# luxo.net
KiCad netlist of a schematic drawn in EAGLE
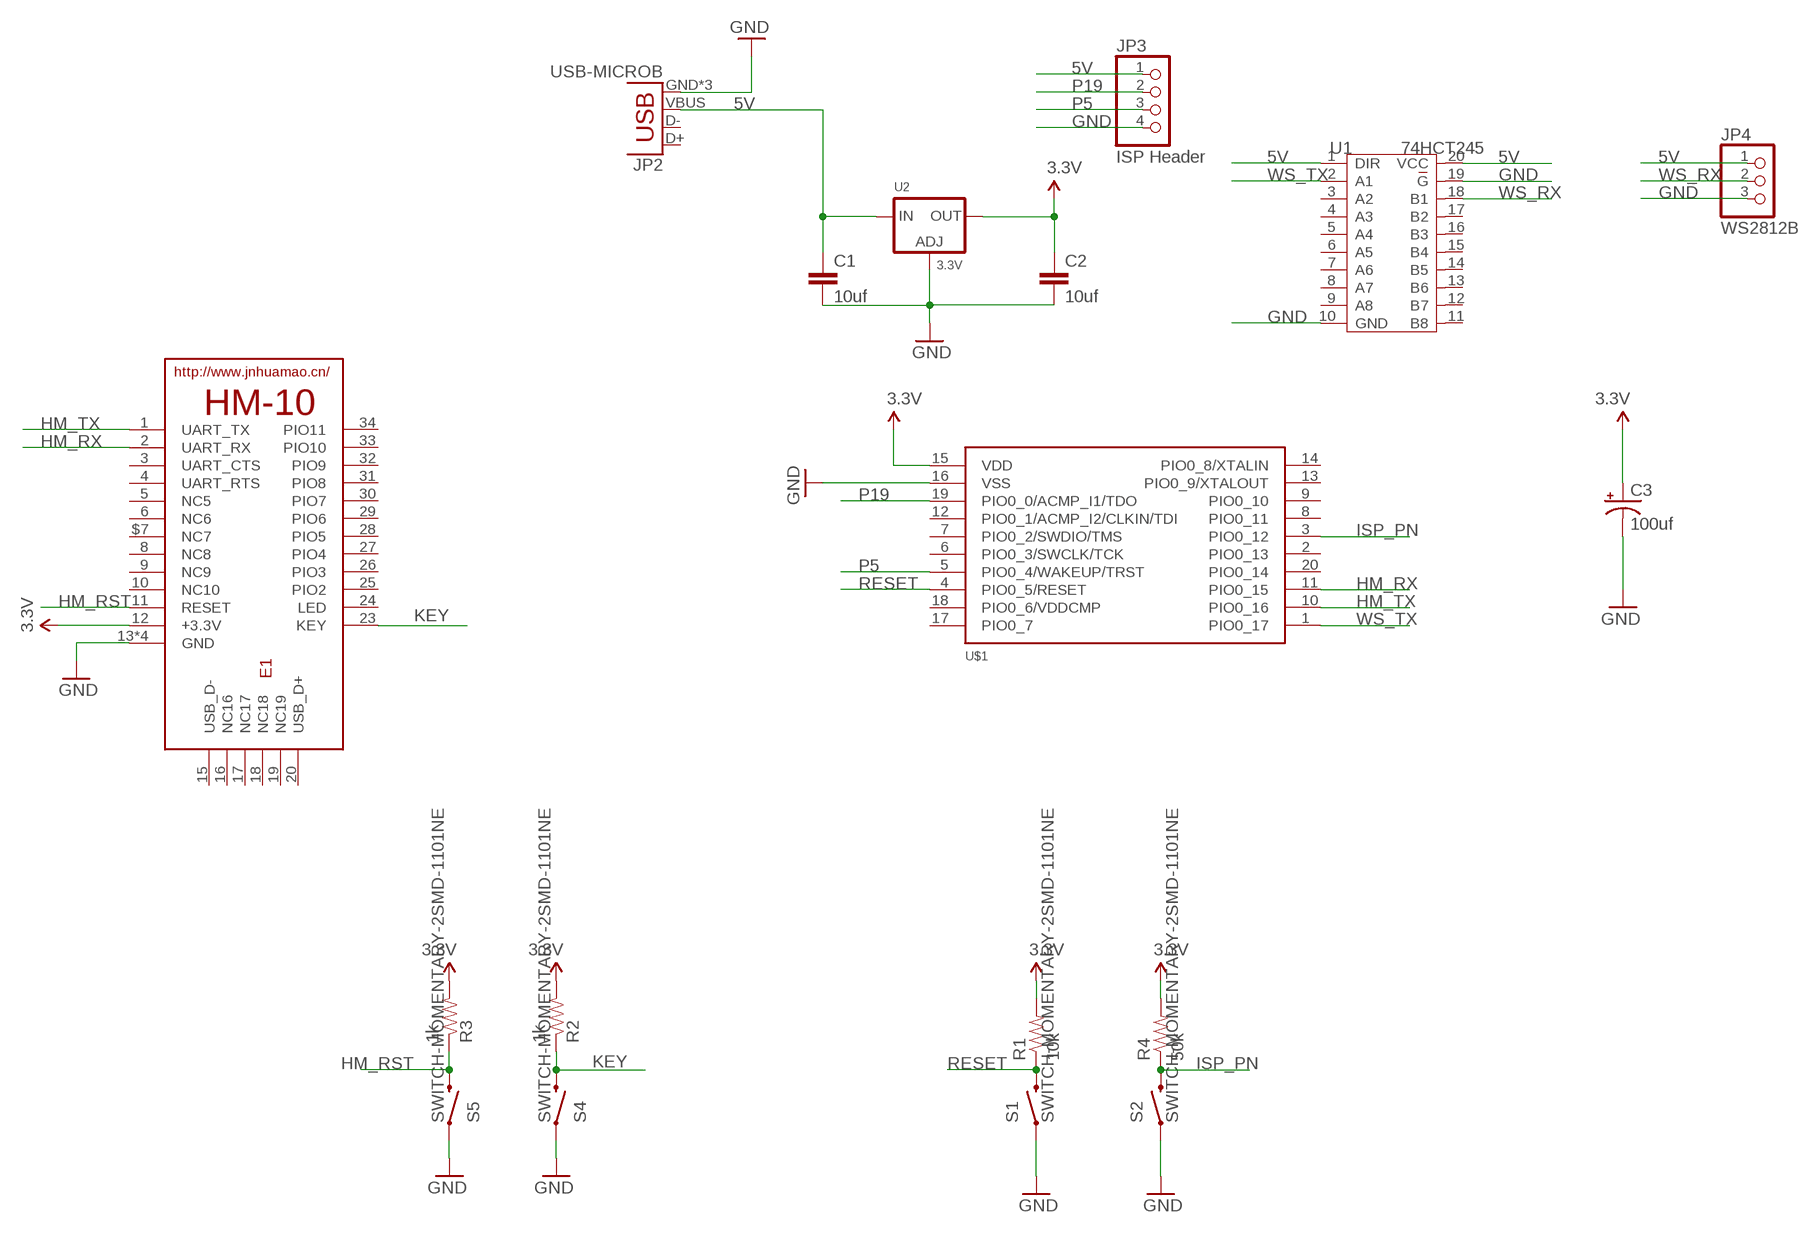
[diagram p0: schematic, sheet 1]

(export (version "E")
  (design (tool "Eeschema 10.0.6"))
  (components
    (comp (ref "C1")
      (value "10uf")
      (footprint "eagle-import:0805-CAP")
      (libsource (lib "eagle-import") (part "10UF10V10%(0805)"))
    )
    (comp (ref "C2")
      (value "10uf")
      (footprint "eagle-import:0805-CAP")
      (libsource (lib "eagle-import") (part "10UF10V10%(0805)"))
    )
    (comp (ref "C3")
      (value "100uf")
      (footprint "eagle-import:CPOL-RADIAL-100UF-25V")
      (libsource (lib "eagle-import") (part "100UF-25V-20%(PTH)"))
    )
    (comp (ref "E1")
      (value "HM-10-BOARD")
      (footprint "eagle-import:26.9X13X2.2_BOARD")
      (libsource (lib "eagle-import") (part "HM-10-BOARD"))
    )
    (comp (ref "JP2")
      (value "USB-MICROB")
      (footprint "eagle-import:USB-MICROB")
      (libsource (lib "eagle-import") (part "USB-MICROB"))
    )
    (comp (ref "JP3")
      (value "ISP Header")
      (footprint "eagle-import:1X04_ROUND")
      (libsource (lib "eagle-import") (part "HEADER-1X4ROUND"))
    )
    (comp (ref "JP4")
      (value "WS2812B")
      (footprint "eagle-import:1X03_OVAL")
      (libsource (lib "eagle-import") (part "HEADER-1X3"))
    )
    (comp (ref "R1")
      (value "10k")
      (footprint "eagle-import:0805")
      (libsource (lib "eagle-import") (part "RESISTOR0805-RES"))
    )
    (comp (ref "R2")
      (value "1k")
      (footprint "eagle-import:0805")
      (libsource (lib "eagle-import") (part "RESISTOR0805-RES"))
    )
    (comp (ref "R3")
      (value "1k")
      (footprint "eagle-import:0805")
      (libsource (lib "eagle-import") (part "RESISTOR0805-RES"))
    )
    (comp (ref "R4")
      (value "50k")
      (footprint "eagle-import:0805")
      (libsource (lib "eagle-import") (part "RESISTOR0805-RES"))
    )
    (comp (ref "S1")
      (value "SWITCH-MOMENTARY-2SMD-1101NE")
      (footprint "eagle-import:TACTILE-SWITCH-1101NE")
      (libsource (lib "eagle-import") (part "SWITCH-MOMENTARY-2SMD-1101NE"))
    )
    (comp (ref "S2")
      (value "SWITCH-MOMENTARY-2SMD-1101NE")
      (footprint "eagle-import:TACTILE-SWITCH-1101NE")
      (libsource (lib "eagle-import") (part "SWITCH-MOMENTARY-2SMD-1101NE"))
    )
    (comp (ref "S4")
      (value "SWITCH-MOMENTARY-2SMD-1101NE")
      (footprint "eagle-import:TACTILE-SWITCH-1101NE")
      (libsource (lib "eagle-import") (part "SWITCH-MOMENTARY-2SMD-1101NE"))
    )
    (comp (ref "S5")
      (value "SWITCH-MOMENTARY-2SMD-1101NE")
      (footprint "eagle-import:TACTILE-SWITCH-1101NE")
      (libsource (lib "eagle-import") (part "SWITCH-MOMENTARY-2SMD-1101NE"))
    )
    (comp (ref "U$1")
      (value "LPC812M101JDH20")
      (footprint "eagle-import:TSSOP20")
      (libsource (lib "eagle-import") (part "LPC812M101JDH20"))
    )
    (comp (ref "U1")
      (value "74HCT245")
      (footprint "eagle-import:SOP20-10.65")
      (libsource (lib "eagle-import") (part "74ACT245-SOP20"))
    )
    (comp (ref "U2")
      (value "3.3V")
      (footprint "eagle-import:SOT223-W")
      (libsource (lib "eagle-import") (part "LM1117SOT223-WAVE"))
    )
  )
  (nets
    (net (code "1") (name "/5V") (class "Default")
      (node (ref "C1") (pin "1") (pinfunction "1_1") (pintype "passive"))
      (node (ref "JP2") (pin "VBUS") (pinfunction "VBUS_VBUS") (pintype "bidirectional"))
      (node (ref "JP3") (pin "1") (pinfunction "1_1") (pintype "passive"))
      (node (ref "JP4") (pin "1") (pinfunction "1_1") (pintype "passive"))
      (node (ref "U1") (pin "1") (pinfunction "DIR_1") (pintype "input"))
      (node (ref "U1") (pin "20") (pinfunction "VCC_20") (pintype "power_in"))
      (node (ref "U2") (pin "3") (pinfunction "IN_3") (pintype "input"))
    )
    (net (code "2") (name "/HM_RST") (class "Default")
      (node (ref "E1") (pin "11") (pinfunction "RESET_11") (pintype "bidirectional"))
      (node (ref "R3") (pin "1") (pinfunction "1_1") (pintype "passive"))
      (node (ref "S5") (pin "2") (pinfunction "2_2") (pintype "passive"))
    )
    (net (code "3") (name "/HM_RX") (class "Default")
      (node (ref "E1") (pin "2") (pinfunction "UART_RX_2") (pintype "bidirectional"))
      (node (ref "U$1") (pin "11") (pinfunction "PIO0_15_11") (pintype "bidirectional"))
    )
    (net (code "4") (name "/HM_TX") (class "Default")
      (node (ref "E1") (pin "1") (pinfunction "UART_TX_1") (pintype "bidirectional"))
      (node (ref "U$1") (pin "10") (pinfunction "PIO0_16_10") (pintype "bidirectional"))
    )
    (net (code "5") (name "/ISP_PN") (class "Default")
      (node (ref "R4") (pin "1") (pinfunction "1_1") (pintype "passive"))
      (node (ref "S2") (pin "2") (pinfunction "2_2") (pintype "passive"))
      (node (ref "U$1") (pin "3") (pinfunction "PIO0_12_3") (pintype "bidirectional"))
    )
    (net (code "6") (name "/KEY") (class "Default")
      (node (ref "E1") (pin "23") (pinfunction "KEY_23") (pintype "bidirectional"))
      (node (ref "R2") (pin "1") (pinfunction "1_1") (pintype "passive"))
      (node (ref "S4") (pin "2") (pinfunction "2_2") (pintype "passive"))
    )
    (net (code "7") (name "/P5") (class "Default")
      (node (ref "JP3") (pin "3") (pinfunction "3_3") (pintype "passive"))
      (node (ref "U$1") (pin "5") (pinfunction "PIO0_4/WAKEUP/TRST_5") (pintype "bidirectional"))
    )
    (net (code "8") (name "/P19") (class "Default")
      (node (ref "JP3") (pin "2") (pinfunction "2_2") (pintype "passive"))
      (node (ref "U$1") (pin "19") (pinfunction "PIO0_0/ACMP_I1/TDO_19") (pintype "bidirectional"))
    )
    (net (code "9") (name "/RESET") (class "Default")
      (node (ref "R1") (pin "1") (pinfunction "1_1") (pintype "passive"))
      (node (ref "S1") (pin "2") (pinfunction "2_2") (pintype "passive"))
      (node (ref "U$1") (pin "4") (pinfunction "PIO0_5/RESET_4") (pintype "bidirectional"))
    )
    (net (code "10") (name "/WS_RX") (class "Default")
      (node (ref "JP4") (pin "2") (pinfunction "2_2") (pintype "passive"))
      (node (ref "U1") (pin "18") (pinfunction "B1_18") (pintype "bidirectional"))
    )
    (net (code "11") (name "/WS_TX") (class "Default")
      (node (ref "U$1") (pin "1") (pinfunction "PIO0_17_1") (pintype "bidirectional"))
      (node (ref "U1") (pin "2") (pinfunction "A1_2") (pintype "bidirectional"))
    )
    (net (code "12") (name "3.3V") (class "Default")
      (node (ref "C2") (pin "1") (pinfunction "1_1") (pintype "passive"))
      (node (ref "C3") (pin "1") (pinfunction "+_1") (pintype "passive"))
      (node (ref "E1") (pin "12") (pinfunction "+3.3V_12") (pintype "bidirectional"))
      (node (ref "R1") (pin "2") (pinfunction "2_2") (pintype "passive"))
      (node (ref "R2") (pin "2") (pinfunction "2_2") (pintype "passive"))
      (node (ref "R3") (pin "2") (pinfunction "2_2") (pintype "passive"))
      (node (ref "R4") (pin "2") (pinfunction "2_2") (pintype "passive"))
      (node (ref "U$1") (pin "15") (pinfunction "VDD_15") (pintype "bidirectional"))
      (node (ref "U2") (pin "2") (pinfunction "OUT_2") (pintype "passive"))
    )
    (net (code "13") (name "GND") (class "Default")
      (node (ref "C1") (pin "2") (pinfunction "2_2") (pintype "passive"))
      (node (ref "C2") (pin "2") (pinfunction "2_2") (pintype "passive"))
      (node (ref "C3") (pin "2") (pinfunction "-_2") (pintype "passive"))
      (node (ref "E1") (pin "13") (pinfunction "GND_13") (pintype "bidirectional"))
      (node (ref "E1") (pin "14") (pinfunction "GND_14") (pintype "bidirectional"))
      (node (ref "E1") (pin "21") (pinfunction "GND_21") (pintype "bidirectional"))
      (node (ref "E1") (pin "22") (pinfunction "GND_22") (pintype "bidirectional"))
      (node (ref "JP2") (pin "GND") (pinfunction "GND_GND") (pintype "bidirectional"))
      (node (ref "JP2") (pin "MT1") (pinfunction "GND_MT1") (pintype "bidirectional"))
      (node (ref "JP2") (pin "MT2") (pinfunction "GND_MT2") (pintype "bidirectional"))
      (node (ref "JP3") (pin "4") (pinfunction "4_4") (pintype "passive"))
      (node (ref "JP4") (pin "3") (pinfunction "3_3") (pintype "passive"))
      (node (ref "S1") (pin "1") (pinfunction "1_1") (pintype "passive"))
      (node (ref "S2") (pin "1") (pinfunction "1_1") (pintype "passive"))
      (node (ref "S4") (pin "1") (pinfunction "1_1") (pintype "passive"))
      (node (ref "S5") (pin "1") (pinfunction "1_1") (pintype "passive"))
      (node (ref "U$1") (pin "16") (pinfunction "VSS_16") (pintype "bidirectional"))
      (node (ref "U1") (pin "10") (pinfunction "GND_10") (pintype "power_in"))
      (node (ref "U1") (pin "19") (pinfunction "G_19") (pintype "bidirectional"))
      (node (ref "U2") (pin "1") (pinfunction "ADJ_1") (pintype "input"))
    )
    (net (code "14") (name "unconnected-(E1-LED-Pad24)") (class "Default")
      (node (ref "E1") (pin "24") (pinfunction "LED_24") (pintype "bidirectional"))
    )
    (net (code "15") (name "unconnected-(E1-NC5-Pad5)") (class "Default")
      (node (ref "E1") (pin "5") (pinfunction "NC5_5") (pintype "bidirectional"))
    )
    (net (code "16") (name "unconnected-(E1-NC6-Pad6)") (class "Default")
      (node (ref "E1") (pin "6") (pinfunction "NC6_6") (pintype "bidirectional"))
    )
    (net (code "17") (name "unconnected-(E1-NC7-Pad$7)") (class "Default")
      (node (ref "E1") (pin "$7") (pinfunction "NC7_$7") (pintype "bidirectional"))
    )
    (net (code "18") (name "unconnected-(E1-NC8-Pad8)") (class "Default")
      (node (ref "E1") (pin "8") (pinfunction "NC8_8") (pintype "bidirectional"))
    )
    (net (code "19") (name "unconnected-(E1-NC9-Pad9)") (class "Default")
      (node (ref "E1") (pin "9") (pinfunction "NC9_9") (pintype "bidirectional"))
    )
    (net (code "20") (name "unconnected-(E1-NC10-Pad10)") (class "Default")
      (node (ref "E1") (pin "10") (pinfunction "NC10_10") (pintype "bidirectional"))
    )
    (net (code "21") (name "unconnected-(E1-NC16-Pad16)") (class "Default")
      (node (ref "E1") (pin "16") (pinfunction "NC16_16") (pintype "bidirectional"))
    )
    (net (code "22") (name "unconnected-(E1-NC17-Pad17)") (class "Default")
      (node (ref "E1") (pin "17") (pinfunction "NC17_17") (pintype "bidirectional"))
    )
    (net (code "23") (name "unconnected-(E1-NC18-Pad18)") (class "Default")
      (node (ref "E1") (pin "18") (pinfunction "NC18_18") (pintype "bidirectional"))
    )
    (net (code "24") (name "unconnected-(E1-NC19-Pad19)") (class "Default")
      (node (ref "E1") (pin "19") (pinfunction "NC19_19") (pintype "bidirectional"))
    )
    (net (code "25") (name "unconnected-(E1-PIO2-Pad25)") (class "Default")
      (node (ref "E1") (pin "25") (pinfunction "PIO2_25") (pintype "bidirectional"))
    )
    (net (code "26") (name "unconnected-(E1-PIO3-Pad26)") (class "Default")
      (node (ref "E1") (pin "26") (pinfunction "PIO3_26") (pintype "bidirectional"))
    )
    (net (code "27") (name "unconnected-(E1-PIO4-Pad27)") (class "Default")
      (node (ref "E1") (pin "27") (pinfunction "PIO4_27") (pintype "bidirectional"))
    )
    (net (code "28") (name "unconnected-(E1-PIO5-Pad28)") (class "Default")
      (node (ref "E1") (pin "28") (pinfunction "PIO5_28") (pintype "bidirectional"))
    )
    (net (code "29") (name "unconnected-(E1-PIO6-Pad29)") (class "Default")
      (node (ref "E1") (pin "29") (pinfunction "PIO6_29") (pintype "bidirectional"))
    )
    (net (code "30") (name "unconnected-(E1-PIO7-Pad30)") (class "Default")
      (node (ref "E1") (pin "30") (pinfunction "PIO7_30") (pintype "bidirectional"))
    )
    (net (code "31") (name "unconnected-(E1-PIO8-Pad31)") (class "Default")
      (node (ref "E1") (pin "31") (pinfunction "PIO8_31") (pintype "bidirectional"))
    )
    (net (code "32") (name "unconnected-(E1-PIO9-Pad32)") (class "Default")
      (node (ref "E1") (pin "32") (pinfunction "PIO9_32") (pintype "bidirectional"))
    )
    (net (code "33") (name "unconnected-(E1-PIO10-Pad33)") (class "Default")
      (node (ref "E1") (pin "33") (pinfunction "PIO10_33") (pintype "bidirectional"))
    )
    (net (code "34") (name "unconnected-(E1-PIO11-Pad34)") (class "Default")
      (node (ref "E1") (pin "34") (pinfunction "PIO11_34") (pintype "bidirectional"))
    )
    (net (code "35") (name "unconnected-(E1-UART_CTS-Pad3)") (class "Default")
      (node (ref "E1") (pin "3") (pinfunction "UART_CTS_3") (pintype "bidirectional"))
    )
    (net (code "36") (name "unconnected-(E1-UART_RTS-Pad4)") (class "Default")
      (node (ref "E1") (pin "4") (pinfunction "UART_RTS_4") (pintype "bidirectional"))
    )
    (net (code "37") (name "unconnected-(E1-USB_D+-Pad20)") (class "Default")
      (node (ref "E1") (pin "20") (pinfunction "USB_D+_20") (pintype "bidirectional"))
    )
    (net (code "38") (name "unconnected-(E1-USB_D--Pad15)") (class "Default")
      (node (ref "E1") (pin "15") (pinfunction "USB_D-_15") (pintype "bidirectional"))
    )
    (net (code "39") (name "unconnected-(JP2-PadD+)") (class "Default")
      (node (ref "JP2") (pin "D+") (pinfunction "D+_D+") (pintype "bidirectional"))
    )
    (net (code "40") (name "unconnected-(JP2-PadD-)") (class "Default")
      (node (ref "JP2") (pin "D-") (pinfunction "D-_D-") (pintype "bidirectional"))
    )
    (net (code "41") (name "unconnected-(U$1-PIO0_1{slash}ACMP_I2{slash}CLKIN{slash}TDI-Pad12)") (class "Default")
      (node (ref "U$1") (pin "12") (pinfunction "PIO0_1/ACMP_I2/CLKIN/TDI_12") (pintype "bidirectional"))
    )
    (net (code "42") (name "unconnected-(U$1-PIO0_2{slash}SWDIO{slash}TMS-Pad7)") (class "Default")
      (node (ref "U$1") (pin "7") (pinfunction "PIO0_2/SWDIO/TMS_7") (pintype "bidirectional"))
    )
    (net (code "43") (name "unconnected-(U$1-PIO0_3{slash}SWCLK{slash}TCK-Pad6)") (class "Default")
      (node (ref "U$1") (pin "6") (pinfunction "PIO0_3/SWCLK/TCK_6") (pintype "bidirectional"))
    )
    (net (code "44") (name "unconnected-(U$1-PIO0_6{slash}VDDCMP-Pad18)") (class "Default")
      (node (ref "U$1") (pin "18") (pinfunction "PIO0_6/VDDCMP_18") (pintype "bidirectional"))
    )
    (net (code "45") (name "unconnected-(U$1-PIO0_7-Pad17)") (class "Default")
      (node (ref "U$1") (pin "17") (pinfunction "PIO0_7_17") (pintype "bidirectional"))
    )
    (net (code "46") (name "unconnected-(U$1-PIO0_8{slash}XTALIN-Pad14)") (class "Default")
      (node (ref "U$1") (pin "14") (pinfunction "PIO0_8/XTALIN_14") (pintype "bidirectional"))
    )
    (net (code "47") (name "unconnected-(U$1-PIO0_9{slash}XTALOUT-Pad13)") (class "Default")
      (node (ref "U$1") (pin "13") (pinfunction "PIO0_9/XTALOUT_13") (pintype "bidirectional"))
    )
    (net (code "48") (name "unconnected-(U$1-PIO0_10-Pad9)") (class "Default")
      (node (ref "U$1") (pin "9") (pinfunction "PIO0_10_9") (pintype "bidirectional"))
    )
    (net (code "49") (name "unconnected-(U$1-PIO0_11-Pad8)") (class "Default")
      (node (ref "U$1") (pin "8") (pinfunction "PIO0_11_8") (pintype "bidirectional"))
    )
    (net (code "50") (name "unconnected-(U$1-PIO0_13-Pad2)") (class "Default")
      (node (ref "U$1") (pin "2") (pinfunction "PIO0_13_2") (pintype "bidirectional"))
    )
    (net (code "51") (name "unconnected-(U$1-PIO0_14-Pad20)") (class "Default")
      (node (ref "U$1") (pin "20") (pinfunction "PIO0_14_20") (pintype "bidirectional"))
    )
    (net (code "52") (name "unconnected-(U1-A2-Pad3)") (class "Default")
      (node (ref "U1") (pin "3") (pinfunction "A2_3") (pintype "bidirectional"))
    )
    (net (code "53") (name "unconnected-(U1-A3-Pad4)") (class "Default")
      (node (ref "U1") (pin "4") (pinfunction "A3_4") (pintype "bidirectional"))
    )
    (net (code "54") (name "unconnected-(U1-A4-Pad5)") (class "Default")
      (node (ref "U1") (pin "5") (pinfunction "A4_5") (pintype "bidirectional"))
    )
    (net (code "55") (name "unconnected-(U1-A5-Pad6)") (class "Default")
      (node (ref "U1") (pin "6") (pinfunction "A5_6") (pintype "bidirectional"))
    )
    (net (code "56") (name "unconnected-(U1-A6-Pad7)") (class "Default")
      (node (ref "U1") (pin "7") (pinfunction "A6_7") (pintype "bidirectional"))
    )
    (net (code "57") (name "unconnected-(U1-A7-Pad8)") (class "Default")
      (node (ref "U1") (pin "8") (pinfunction "A7_8") (pintype "bidirectional"))
    )
    (net (code "58") (name "unconnected-(U1-A8-Pad9)") (class "Default")
      (node (ref "U1") (pin "9") (pinfunction "A8_9") (pintype "bidirectional"))
    )
    (net (code "59") (name "unconnected-(U1-B2-Pad17)") (class "Default")
      (node (ref "U1") (pin "17") (pinfunction "B2_17") (pintype "bidirectional"))
    )
    (net (code "60") (name "unconnected-(U1-B3-Pad16)") (class "Default")
      (node (ref "U1") (pin "16") (pinfunction "B3_16") (pintype "bidirectional"))
    )
    (net (code "61") (name "unconnected-(U1-B4-Pad15)") (class "Default")
      (node (ref "U1") (pin "15") (pinfunction "B4_15") (pintype "bidirectional"))
    )
    (net (code "62") (name "unconnected-(U1-B5-Pad14)") (class "Default")
      (node (ref "U1") (pin "14") (pinfunction "B5_14") (pintype "bidirectional"))
    )
    (net (code "63") (name "unconnected-(U1-B6-Pad13)") (class "Default")
      (node (ref "U1") (pin "13") (pinfunction "B6_13") (pintype "bidirectional"))
    )
    (net (code "64") (name "unconnected-(U1-B7-Pad12)") (class "Default")
      (node (ref "U1") (pin "12") (pinfunction "B7_12") (pintype "bidirectional"))
    )
    (net (code "65") (name "unconnected-(U1-B8-Pad11)") (class "Default")
      (node (ref "U1") (pin "11") (pinfunction "B8_11") (pintype "bidirectional"))
    )
  )
)
